# trans.net
KiCad netlist of a schematic drawn in EAGLE
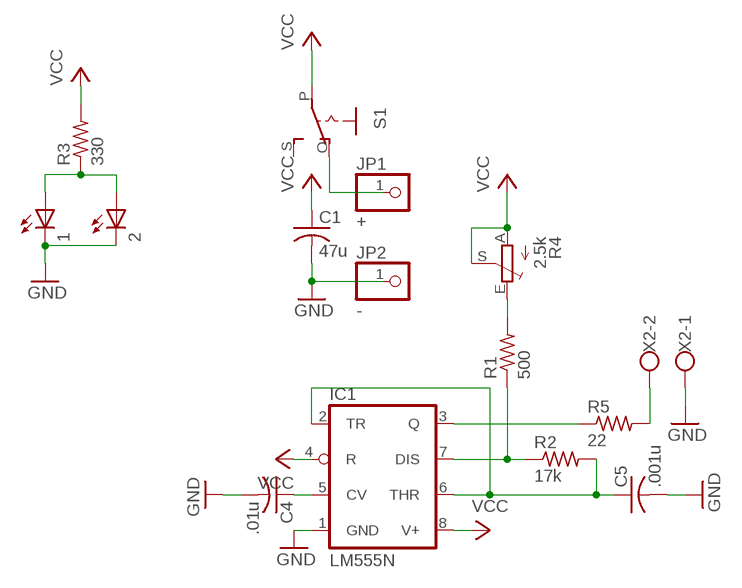
[diagram p0: schematic, sheet 1]

(export (version "E")
  (design (tool "Eeschema 10.0.6"))
  (components
    (comp (ref "1")
      (value "LED3MM")
      (footprint "eagle-import:LED3MM")
      (libsource (lib "eagle-import") (part "LED3MM"))
    )
    (comp (ref "2")
      (value "LED3MM")
      (footprint "eagle-import:LED3MM")
      (libsource (lib "eagle-import") (part "LED3MM"))
    )
    (comp (ref "C1")
      (value "47u")
      (footprint "eagle-import:C050-025X075")
      (libsource (lib "eagle-import") (part "C-US050-025X075"))
    )
    (comp (ref "C4")
      (value ".01u")
      (footprint "eagle-import:C025-025X050")
      (libsource (lib "eagle-import") (part "C-US025-025X050"))
    )
    (comp (ref "C5")
      (value ".001u")
      (footprint "eagle-import:C025-025X050")
      (libsource (lib "eagle-import") (part "C-US025-025X050"))
    )
    (comp (ref "IC1")
      (value "LM555N")
      (footprint "eagle-import:DIL08")
      (libsource (lib "eagle-import") (part "555NLM"))
    )
    (comp (ref "JP1")
      (value "+")
      (footprint "eagle-import:1X01")
      (libsource (lib "eagle-import") (part "PINHD-1X1"))
    )
    (comp (ref "JP2")
      (value "-")
      (footprint "eagle-import:1X01")
      (libsource (lib "eagle-import") (part "PINHD-1X1"))
    )
    (comp (ref "R1")
      (value "500")
      (footprint "eagle-import:0207_10")
      (libsource (lib "eagle-import") (part "R-US_0207/10"))
    )
    (comp (ref "R2")
      (value "17k")
      (footprint "eagle-import:0207_10")
      (libsource (lib "eagle-import") (part "R-US_0207/10"))
    )
    (comp (ref "R3")
      (value "330")
      (footprint "eagle-import:0207_10")
      (libsource (lib "eagle-import") (part "R-US_0207/10"))
    )
    (comp (ref "R4")
      (value "2.5k")
      (footprint "eagle-import:CA9V")
      (libsource (lib "eagle-import") (part "TRIM_EU-CA9V"))
    )
    (comp (ref "R5")
      (value "22")
      (footprint "eagle-import:0207_10")
      (libsource (lib "eagle-import") (part "rcl_334_R-US_0207/10"))
    )
    (comp (ref "S1")
      (value "EG1218S")
      (footprint "eagle-import:EG1218")
      (libsource (lib "eagle-import") (part "EG1218S"))
    )
    (comp (ref "X2")
      (value "W237-102")
      (footprint "eagle-import:W237-102")
      (fields (field (name "MPN") "237-102"))
      (libsource (lib "eagle-import") (part "W237-102"))
    )
  )
  (nets
    (net (code "1") (name "GND") (class "Default")
      (node (ref "1") (pin "K") (pinfunction "C_K") (pintype "passive"))
      (node (ref "2") (pin "K") (pinfunction "C_K") (pintype "passive"))
      (node (ref "C1") (pin "2") (pinfunction "2_2") (pintype "passive"))
      (node (ref "C4") (pin "2") (pinfunction "2_2") (pintype "passive"))
      (node (ref "C5") (pin "2") (pinfunction "2_2") (pintype "passive"))
      (node (ref "IC1") (pin "1") (pinfunction "GND_1") (pintype "power_in"))
      (node (ref "JP2") (pin "1") (pinfunction "1_1") (pintype "passive"))
      (node (ref "X2") (pin "1") (pinfunction "KL_1") (pintype "passive"))
    )
    (net (code "2") (name "Net-(1-PadA)") (class "Default")
      (node (ref "1") (pin "A") (pinfunction "A_A") (pintype "passive"))
      (node (ref "2") (pin "A") (pinfunction "A_A") (pintype "passive"))
      (node (ref "R3") (pin "1") (pinfunction "1_1") (pintype "passive"))
    )
    (net (code "3") (name "Net-(IC1-CV)") (class "Default")
      (node (ref "C4") (pin "1") (pinfunction "1_1") (pintype "passive"))
      (node (ref "IC1") (pin "5") (pinfunction "CV_5") (pintype "input"))
    )
    (net (code "4") (name "Net-(IC1-DIS)") (class "Default")
      (node (ref "IC1") (pin "7") (pinfunction "DIS_7") (pintype "input"))
      (node (ref "R1") (pin "1") (pinfunction "1_1") (pintype "passive"))
      (node (ref "R2") (pin "1") (pinfunction "1_1") (pintype "passive"))
    )
    (net (code "5") (name "Net-(IC1-Q)") (class "Default")
      (node (ref "IC1") (pin "3") (pinfunction "Q_3") (pintype "output"))
      (node (ref "R5") (pin "1") (pinfunction "1_1") (pintype "passive"))
    )
    (net (code "6") (name "Net-(IC1-THR)") (class "Default")
      (node (ref "C5") (pin "1") (pinfunction "1_1") (pintype "passive"))
      (node (ref "IC1") (pin "2") (pinfunction "TR_2") (pintype "input"))
      (node (ref "IC1") (pin "6") (pinfunction "THR_6") (pintype "input"))
      (node (ref "R2") (pin "2") (pinfunction "2_2") (pintype "passive"))
    )
    (net (code "7") (name "Net-(JP1-Pad1)") (class "Default")
      (node (ref "JP1") (pin "1") (pinfunction "1_1") (pintype "passive"))
      (node (ref "S1") (pin "O") (pinfunction "O_O") (pintype "passive"))
    )
    (net (code "8") (name "Net-(R1-Pad2)") (class "Default")
      (node (ref "R1") (pin "2") (pinfunction "2_2") (pintype "passive"))
      (node (ref "R4") (pin "E") (pinfunction "E_E") (pintype "passive"))
    )
    (net (code "9") (name "Net-(X2B-KL)") (class "Default")
      (node (ref "R5") (pin "2") (pinfunction "2_2") (pintype "passive"))
      (node (ref "X2") (pin "2") (pinfunction "KL_2") (pintype "passive"))
    )
    (net (code "10") (name "VCC") (class "Default")
      (node (ref "C1") (pin "1") (pinfunction "1_1") (pintype "passive"))
      (node (ref "IC1") (pin "4") (pinfunction "R_4") (pintype "input"))
      (node (ref "IC1") (pin "8") (pinfunction "V+_8") (pintype "power_in"))
      (node (ref "R3") (pin "2") (pinfunction "2_2") (pintype "passive"))
      (node (ref "R4") (pin "A") (pinfunction "A_A") (pintype "passive"))
      (node (ref "R4") (pin "S") (pinfunction "S_S") (pintype "passive"))
      (node (ref "S1") (pin "P") (pinfunction "P_P") (pintype "passive"))
    )
    (net (code "11") (name "unconnected-(S1-PadS)") (class "Default")
      (node (ref "S1") (pin "S") (pinfunction "S_S") (pintype "passive"))
    )
  )
)
